# Page05_DDR4L_eMMC.net
KiCad netlist of a schematic drawn in Altium Designer
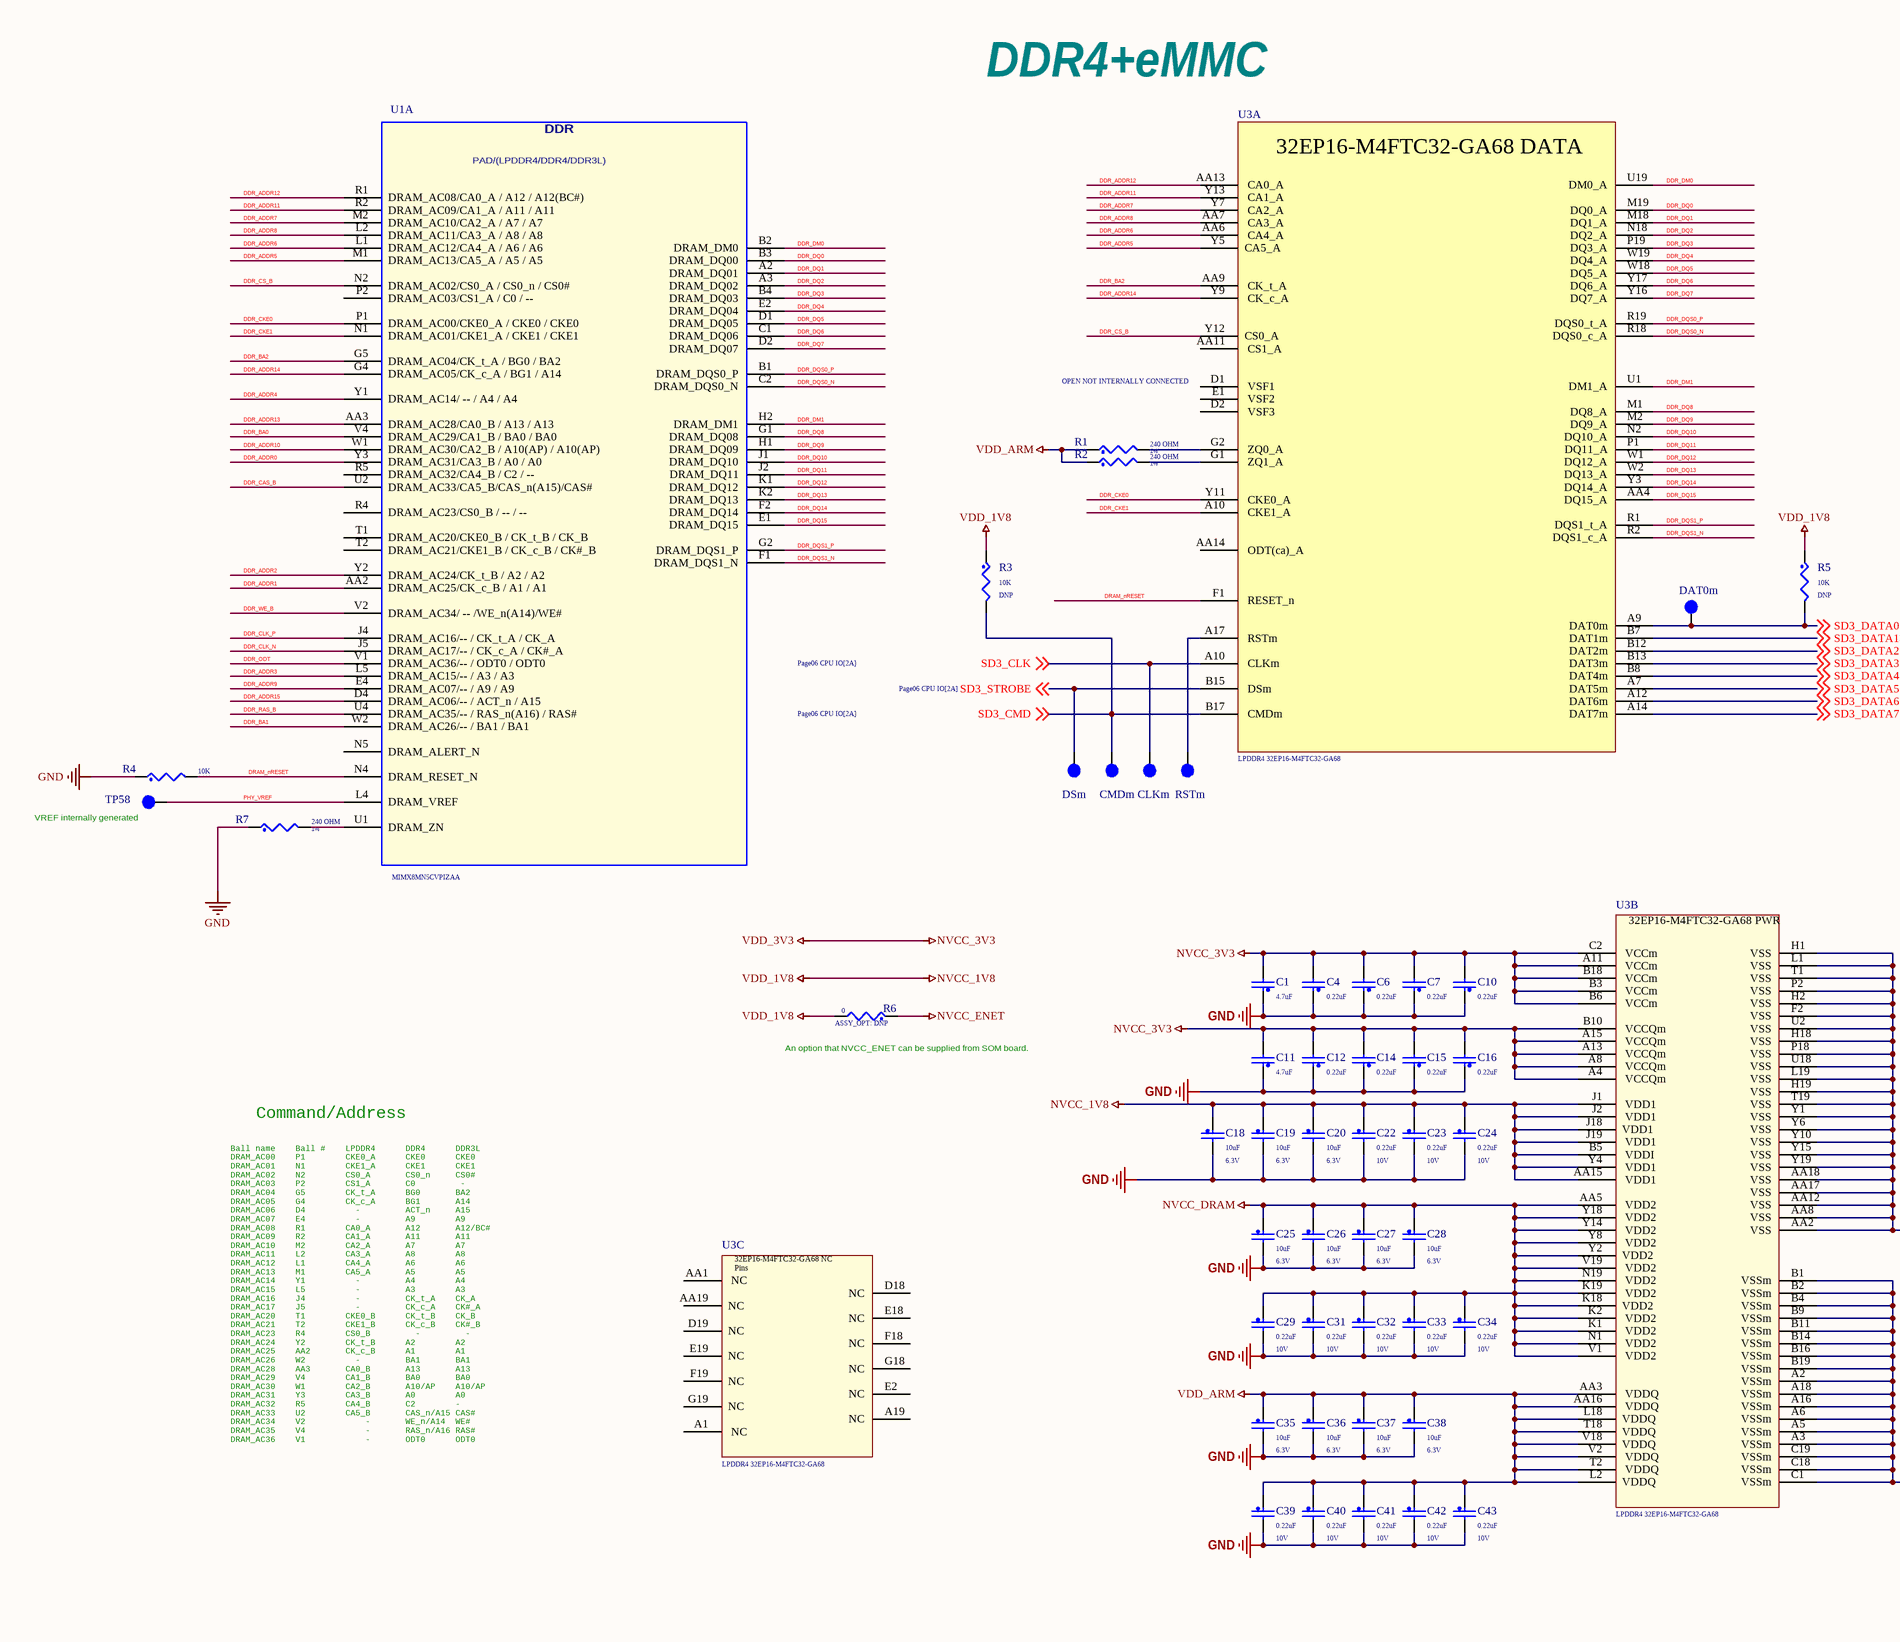
[diagram p0: Page05 DDR4L+eMMC.SchDoc, left]
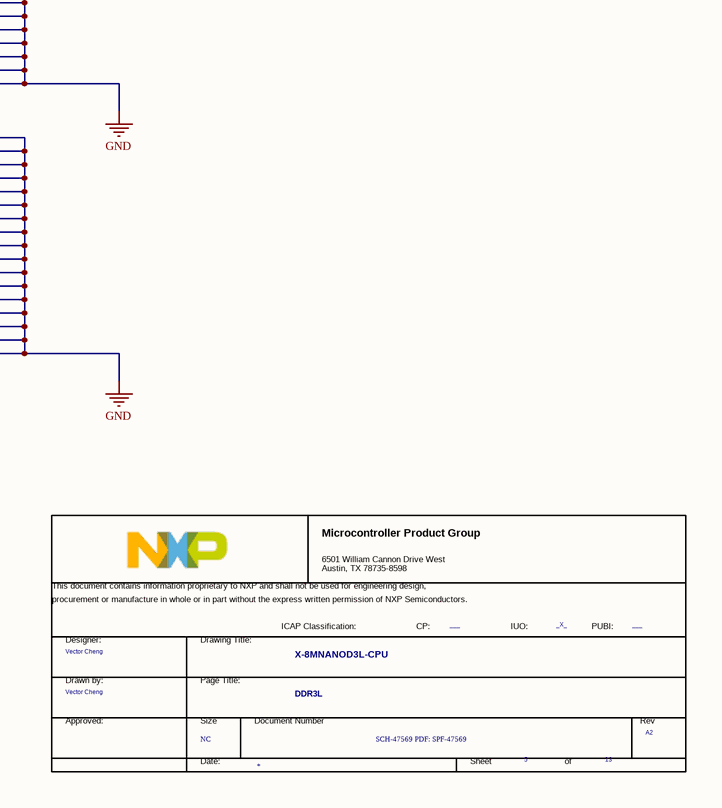
[diagram p1: Page05 DDR4L+eMMC.SchDoc, right]

(export (version "E")
  (design (tool "Eeschema 10.0.6"))
  (components
    (comp (ref "C1") (value "4.7uF") (footprint "0402_CC - C") (libsource (lib "AA_iMX8_M_") (part "CAP_NP")))
    (comp (ref "C4")
      (value "0.22uF")
      (footprint "0201_CC - C")
      (libsource (lib "AA_iMX8_M_") (part "CAP_NP"))
    )
    (comp (ref "C6")
      (value "0.22uF")
      (footprint "0201_CC - C")
      (libsource (lib "AA_iMX8_M_") (part "CAP_NP"))
    )
    (comp (ref "C7")
      (value "0.22uF")
      (footprint "0201_CC - C")
      (libsource (lib "AA_iMX8_M_") (part "CAP_NP"))
    )
    (comp (ref "C10")
      (value "0.22uF")
      (footprint "0201_CC - C")
      (libsource (lib "AA_iMX8_M_") (part "CAP_NP"))
    )
    (comp (ref "C11")
      (value "4.7uF")
      (footprint "0402_CC - C")
      (libsource (lib "AA_iMX8_M_") (part "CAP_NP"))
    )
    (comp (ref "C12")
      (value "0.22uF")
      (footprint "0201_CC - C")
      (libsource (lib "AA_iMX8_M_") (part "CAP_NP"))
    )
    (comp (ref "C14")
      (value "0.22uF")
      (footprint "0201_CC - C")
      (libsource (lib "AA_iMX8_M_") (part "CAP_NP"))
    )
    (comp (ref "C15")
      (value "0.22uF")
      (footprint "0201_CC - C")
      (libsource (lib "AA_iMX8_M_") (part "CAP_NP"))
    )
    (comp (ref "C16")
      (value "0.22uF")
      (footprint "0201_CC - C")
      (libsource (lib "AA_iMX8_M_") (part "CAP_NP"))
    )
    (comp (ref "C18")
      (value "10uF")
      (footprint "0402_CC - C")
      (fields (field (name "VOLTAGE") "6.3V"))
      (libsource (lib "AA_iMX8_M_") (part "CAP_NP"))
    )
    (comp (ref "C19")
      (value "10uF")
      (footprint "0402_CC - C")
      (fields (field (name "VOLTAGE") "6.3V"))
      (libsource (lib "AA_iMX8_M_") (part "CAP_NP"))
    )
    (comp (ref "C20")
      (value "10uF")
      (footprint "0402_CC - C")
      (fields (field (name "VOLTAGE") "6.3V"))
      (libsource (lib "AA_iMX8_M_") (part "CAP_NP"))
    )
    (comp (ref "C22")
      (value "0.22uF")
      (footprint "0201_CC - C")
      (fields (field (name "VOLTAGE") "10V"))
      (libsource (lib "AA_iMX8_M_") (part "CAP_NP"))
    )
    (comp (ref "C23")
      (value "0.22uF")
      (footprint "0201_CC - C")
      (fields (field (name "VOLTAGE") "10V"))
      (libsource (lib "AA_iMX8_M_") (part "CAP_NP"))
    )
    (comp (ref "C24")
      (value "0.22uF")
      (footprint "0201_CC - C")
      (fields (field (name "VOLTAGE") "10V"))
      (libsource (lib "AA_iMX8_M_") (part "CAP_NP"))
    )
    (comp (ref "C25")
      (value "10uF")
      (footprint "0402_CC - C")
      (fields (field (name "VOLTAGE") "6.3V"))
      (libsource (lib "AA_iMX8_M_") (part "CAP_NP"))
    )
    (comp (ref "C26")
      (value "10uF")
      (footprint "0402_CC - C")
      (fields (field (name "VOLTAGE") "6.3V"))
      (libsource (lib "AA_iMX8_M_") (part "CAP_NP"))
    )
    (comp (ref "C27")
      (value "10uF")
      (footprint "0402_CC - C")
      (fields (field (name "VOLTAGE") "6.3V"))
      (libsource (lib "AA_iMX8_M_") (part "CAP_NP"))
    )
    (comp (ref "C28")
      (value "10uF")
      (footprint "0402_CC - C")
      (fields (field (name "VOLTAGE") "6.3V"))
      (libsource (lib "AA_iMX8_M_") (part "CAP_NP"))
    )
    (comp (ref "C29")
      (value "0.22uF")
      (footprint "0201_CC - C")
      (fields (field (name "VOLTAGE") "10V"))
      (libsource (lib "AA_iMX8_M_") (part "CAP_NP"))
    )
    (comp (ref "C31")
      (value "0.22uF")
      (footprint "0201_CC - C")
      (fields (field (name "VOLTAGE") "10V"))
      (libsource (lib "AA_iMX8_M_") (part "CAP_NP"))
    )
    (comp (ref "C32")
      (value "0.22uF")
      (footprint "0201_CC - C")
      (fields (field (name "VOLTAGE") "10V"))
      (libsource (lib "AA_iMX8_M_") (part "CAP_NP"))
    )
    (comp (ref "C33")
      (value "0.22uF")
      (footprint "0201_CC - C")
      (fields (field (name "VOLTAGE") "10V"))
      (libsource (lib "AA_iMX8_M_") (part "CAP_NP"))
    )
    (comp (ref "C34")
      (value "0.22uF")
      (footprint "0201_CC - C")
      (fields (field (name "VOLTAGE") "10V"))
      (libsource (lib "AA_iMX8_M_") (part "CAP_NP"))
    )
    (comp (ref "C35")
      (value "10uF")
      (footprint "0402_CC - C")
      (fields (field (name "VOLTAGE") "6.3V"))
      (libsource (lib "AA_iMX8_M_") (part "CAP_NP"))
    )
    (comp (ref "C36")
      (value "10uF")
      (footprint "0402_CC - C")
      (fields (field (name "VOLTAGE") "6.3V"))
      (libsource (lib "AA_iMX8_M_") (part "CAP_NP"))
    )
    (comp (ref "C37")
      (value "10uF")
      (footprint "0402_CC - C")
      (fields (field (name "VOLTAGE") "6.3V"))
      (libsource (lib "AA_iMX8_M_") (part "CAP_NP"))
    )
    (comp (ref "C38")
      (value "10uF")
      (footprint "0402_CC - C")
      (fields (field (name "VOLTAGE") "6.3V"))
      (libsource (lib "AA_iMX8_M_") (part "CAP_NP"))
    )
    (comp (ref "C39")
      (value "0.22uF")
      (footprint "0201_CC - C")
      (fields (field (name "VOLTAGE") "10V"))
      (libsource (lib "AA_iMX8_M_") (part "CAP_NP"))
    )
    (comp (ref "C40")
      (value "0.22uF")
      (footprint "0201_CC - C")
      (fields (field (name "VOLTAGE") "10V"))
      (libsource (lib "AA_iMX8_M_") (part "CAP_NP"))
    )
    (comp (ref "C41")
      (value "0.22uF")
      (footprint "0201_CC - C")
      (fields (field (name "VOLTAGE") "10V"))
      (libsource (lib "AA_iMX8_M_") (part "CAP_NP"))
    )
    (comp (ref "C42")
      (value "0.22uF")
      (footprint "0201_CC - C")
      (fields (field (name "VOLTAGE") "10V"))
      (libsource (lib "AA_iMX8_M_") (part "CAP_NP"))
    )
    (comp (ref "C43")
      (value "0.22uF")
      (footprint "0201_CC - C")
      (fields (field (name "VOLTAGE") "10V"))
      (libsource (lib "AA_iMX8_M_") (part "CAP_NP"))
    )
    (comp (ref "CLKm")
      (value "tpad_020")
      (footprint "tpad_020")
      (description "TEST POINT PAD 0.5MM DIA SMT, NO PART TO ORDER")
      (libsource (lib "*") (part "TESTLOOP"))
    )
    (comp (ref "CMDm")
      (value "TPAD_015")
      (footprint "TPAD_015")
      (description "TEST POINT PAD 15MIL DIA SMT, NO PART TO ORDER")
      (libsource (lib "*") (part "TESTLOOP"))
    )
    (comp (ref "DAT0m")
      (value "tpad_020")
      (footprint "tpad_020")
      (description "TEST POINT PAD 0.5MM DIA SMT, NO PART TO ORDER")
      (libsource (lib "*") (part "TESTLOOP"))
    )
    (comp (ref "DSm")
      (value "TPAD_015")
      (footprint "TPAD_015")
      (description "TEST POINT PAD 15MIL DIA SMT, NO PART TO ORDER")
      (libsource (lib "*") (part "TESTLOOP"))
    )
    (comp (ref "R1")
      (value "240 OHM")
      (footprint "0201_RES")
      (description "RES MF 240 OHM 1/20W 1% 0201")
      (fields (field (name "VOLTAGE") "25V") (field (name "TOLERANCE") "1%"))
      (libsource (lib "*") (part "RES"))
    )
    (comp (ref "R2")
      (value "240 OHM")
      (footprint "0201_RES")
      (description "RES MF 240 OHM 1/20W 1% 0201")
      (fields (field (name "VOLTAGE") "25V") (field (name "TOLERANCE") "1%"))
      (libsource (lib "*") (part "RES"))
    )
    (comp (ref "R3")
      (value "10K")
      (footprint "0201_RES")
      (description "RES MF 10K 1/20W 5% 0201")
      (fields (field (name "ASSY_OPT") "DNP") (field (name "TOLERANCE") "5%"))
      (libsource (lib "*") (part "RES"))
    )
    (comp (ref "R4")
      (value "10K")
      (footprint "0201_RES")
      (description "RES MF 10K 1/20W 5% 0201")
      (fields (field (name "TOLERANCE") "5%"))
      (libsource (lib "*") (part "RES"))
    )
    (comp (ref "R5")
      (value "10K")
      (footprint "0201_RES")
      (description "RES MF 10K 1/20W 5% 0201")
      (fields (field (name "ASSY_OPT") "DNP") (field (name "TOLERANCE") "5%"))
      (libsource (lib "*") (part "RES"))
    )
    (comp (ref "R6")
      (value "0")
      (footprint "0402_CC_RES")
      (description "RES MF ZERO OHM 1/16W 5% 0402")
      (fields
        (field (name "ASSY_OPT") "DNP")
        (field (name "TOLERANCE") "5%")
        (field (name "VOLTAGE") "1/16W")
      )
      (libsource (lib "*") (part "RES"))
    )
    (comp (ref "R7")
      (value "240 OHM")
      (footprint "0201_RES")
      (description "RES MF 240 OHM 1/20W 1% 0201")
      (fields (field (name "VOLTAGE") "25V") (field (name "TOLERANCE") "1%"))
      (libsource (lib "*") (part "RES"))
    )
    (comp (ref "RSTm")
      (value "tpad_020")
      (footprint "tpad_020")
      (description "TEST POINT PAD 0.5MM DIA SMT, NO PART TO ORDER")
      (libsource (lib "*") (part "TESTLOOP"))
    )
    (comp (ref "TP58")
      (value "tpad_020")
      (footprint "tpad_020")
      (description "TEST POINT PAD 0.5MM DIA SMT, NO PART TO ORDER")
      (libsource (lib "*") (part "TESTLOOP"))
    )
    (comp (ref "U1")
      (value "MIMX8MN5CVPIZAA")
      (footprint "BGA306C50P21X21_1100X1100X101")
      (description "IC CPU QUAD CORTEX A53+M7 1.4GHZ -- BGA306")
      (libsource (lib "*") (part "MIMX8MN"))
    )
    (comp (ref "U3")
      (value "LPDDR4 32EP16-M4FTC32-GA68")
      (footprint "FBGA144C40P19X21_800X950X80")
      (libsource (lib "") (part "LPDDR4 32EP16-M4FTC32-GA68_1"))
    )
  )
  (nets
    (net (code "1") (name "/DDR_ADDR0") (class "Default")
      (node (ref "U1") (pin "Y3") (pinfunction "DRAM_AC31/CA3_B_/_A0_/_A0_Y3") (pintype "passive"))
    )
    (net (code "2") (name "/DDR_ADDR1") (class "Default")
      (node (ref "U1") (pin "AA2") (pinfunction "DRAM_AC25/CK_c_B_/_A1_/_A1_AA2") (pintype "passive"))
    )
    (net (code "3") (name "/DDR_ADDR2") (class "Default")
      (node (ref "U1") (pin "Y2") (pinfunction "DRAM_AC24/CK_t_B_/_A2_/_A2_Y2") (pintype "passive"))
    )
    (net (code "4") (name "/DDR_ADDR3") (class "Default")
      (node (ref "U1") (pin "L5") (pinfunction "DRAM_AC15/--_/_A3_/_A3_L5") (pintype "passive"))
    )
    (net (code "5") (name "/DDR_ADDR4") (class "Default")
      (node (ref "U1") (pin "Y1") (pinfunction "DRAM_AC14/_--_/_A4_/_A4_Y1") (pintype "passive"))
    )
    (net (code "6") (name "/DDR_ADDR5") (class "Default")
      (node (ref "U1") (pin "M1") (pinfunction "DRAM_AC13/CA5_A_/_A5_/_A5_M1") (pintype "passive"))
      (node (ref "U3") (pin "Y5") (pinfunction "CA5_A_Y5") (pintype "passive"))
    )
    (net (code "7") (name "/DDR_ADDR6") (class "Default")
      (node (ref "U1") (pin "L1") (pinfunction "DRAM_AC12/CA4_A_/_A6_/_A6_L1") (pintype "passive"))
      (node (ref "U3") (pin "AA6") (pinfunction "_CA4_A_AA6") (pintype "passive"))
    )
    (net (code "8") (name "/DDR_ADDR7") (class "Default")
      (node (ref "U1") (pin "M2") (pinfunction "DRAM_AC10/CA2_A_/_A7_/_A7_M2") (pintype "passive"))
      (node (ref "U3") (pin "Y7") (pinfunction "_CA2_A_Y7") (pintype "passive"))
    )
    (net (code "9") (name "/DDR_ADDR8") (class "Default")
      (node (ref "U1") (pin "L2") (pinfunction "DRAM_AC11/CA3_A_/_A8_/_A8_L2") (pintype "passive"))
      (node (ref "U3") (pin "AA7") (pinfunction "_CA3_A_AA7") (pintype "passive"))
    )
    (net (code "10") (name "/DDR_ADDR9") (class "Default")
      (node (ref "U1") (pin "E4") (pinfunction "DRAM_AC07/--_/_A9_/_A9_E4") (pintype "passive"))
    )
    (net (code "11") (name "/DDR_ADDR10") (class "Default")
      (node (ref "U1") (pin "W1") (pinfunction "DRAM_AC30/CA2_B_/_A10(AP)_/_A10(AP)_W1") (pintype "passive"))
    )
    (net (code "12") (name "/DDR_ADDR11") (class "Default")
      (node (ref "U1") (pin "R2") (pinfunction "DRAM_AC09/CA1_A_/_A11_/_A11_R2") (pintype "passive"))
      (node (ref "U3") (pin "Y13") (pinfunction "_CA1_A_Y13") (pintype "passive"))
    )
    (net (code "13") (name "/DDR_ADDR12") (class "Default")
      (node (ref "U1") (pin "R1") (pinfunction "DRAM_AC08/CA0_A_/_A12_/_A12(BC#)_R1") (pintype "passive"))
      (node (ref "U3") (pin "AA13") (pinfunction "_CA0_A_AA13") (pintype "passive"))
    )
    (net (code "14") (name "/DDR_ADDR13") (class "Default")
      (node (ref "U1") (pin "AA3") (pinfunction "DRAM_AC28/CA0_B_/_A13_/_A13_AA3") (pintype "passive"))
    )
    (net (code "15") (name "/DDR_ADDR14") (class "Default")
      (node (ref "U1") (pin "G4") (pinfunction "DRAM_AC05/CK_c_A_/_BG1_/_A14_G4") (pintype "passive"))
      (node (ref "U3") (pin "Y9") (pinfunction "_CK_c_A_Y9") (pintype "passive"))
    )
    (net (code "16") (name "/DDR_ADDR15") (class "Default")
      (node (ref "U1") (pin "D4") (pinfunction "DRAM_AC06/--_/_ACT_n_/_A15_D4") (pintype "passive"))
    )
    (net (code "17") (name "/DDR_BA0") (class "Default")
      (node (ref "U1") (pin "V4") (pinfunction "DRAM_AC29/CA1_B_/_BA0_/_BA0_V4") (pintype "passive"))
    )
    (net (code "18") (name "/DDR_BA1") (class "Default")
      (node (ref "U1") (pin "W2") (pinfunction "DRAM_AC26/--_/_BA1_/_BA1_W2") (pintype "passive"))
    )
    (net (code "19") (name "/DDR_BA2") (class "Default")
      (node (ref "U1") (pin "G5") (pinfunction "DRAM_AC04/CK_t_A_/_BG0_/_BA2_G5") (pintype "passive"))
      (node (ref "U3") (pin "AA9") (pinfunction "_CK_t_A_AA9") (pintype "passive"))
    )
    (net (code "20") (name "/DDR_CAS_B") (class "Default")
      (node (ref "U1") (pin "U2") (pinfunction "DRAM_AC33/CA5_B/CAS_n(A15)/CAS#_U2") (pintype "passive"))
    )
    (net (code "21") (name "/DDR_CKE0") (class "Default")
      (node (ref "U1") (pin "P1") (pinfunction "DRAM_AC00/CKE0_A_/_CKE0_/_CKE0_P1") (pintype "passive"))
      (node (ref "U3") (pin "Y11") (pinfunction "_CKE0_A_Y11") (pintype "passive"))
    )
    (net (code "22") (name "/DDR_CKE1") (class "Default")
      (node (ref "U1") (pin "N1") (pinfunction "DRAM_AC01/CKE1_A_/_CKE1_/_CKE1_N1") (pintype "passive"))
      (node (ref "U3") (pin "A10") (pinfunction "_CKE1_A_A10") (pintype "passive"))
    )
    (net (code "23") (name "/DDR_CLK_N") (class "Default")
      (node (ref "U1") (pin "J5") (pinfunction "DRAM_AC17/--_/_CK_c_A_/_CK#_A_J5") (pintype "passive"))
    )
    (net (code "24") (name "/DDR_CLK_P") (class "Default")
      (node (ref "U1") (pin "J4") (pinfunction "DRAM_AC16/--_/_CK_t_A_/_CK_A_J4") (pintype "passive"))
    )
    (net (code "25") (name "/DDR_CS_B") (class "Default")
      (node (ref "U1") (pin "N2") (pinfunction "DRAM_AC02/CS0_A_/_CS0_n_/_CS0#_N2") (pintype "passive"))
      (node (ref "U3") (pin "Y12") (pinfunction "CS0_A_Y12") (pintype "passive"))
    )
    (net (code "26") (name "/DDR_DM0") (class "Default")
      (node (ref "U1") (pin "B2") (pinfunction "DRAM_DM0_B2") (pintype "passive"))
      (node (ref "U3") (pin "U19") (pinfunction "_DM0_A_U19") (pintype "passive"))
    )
    (net (code "27") (name "/DDR_DM1") (class "Default")
      (node (ref "U1") (pin "H2") (pinfunction "DRAM_DM1_H2") (pintype "passive"))
      (node (ref "U3") (pin "U1") (pinfunction "_DM1_A_U1") (pintype "passive"))
    )
    (net (code "28") (name "/DDR_DQ0") (class "Default")
      (node (ref "U1") (pin "B3") (pinfunction "DRAM_DQ00_B3") (pintype "passive"))
      (node (ref "U3") (pin "M19") (pinfunction "_DQ0_A_M19") (pintype "passive"))
    )
    (net (code "29") (name "/DDR_DQ1") (class "Default")
      (node (ref "U1") (pin "A2") (pinfunction "DRAM_DQ01_A2") (pintype "passive"))
      (node (ref "U3") (pin "M18") (pinfunction "DQ1_A_M18") (pintype "passive"))
    )
    (net (code "30") (name "/DDR_DQ2") (class "Default")
      (node (ref "U1") (pin "A3") (pinfunction "DRAM_DQ02_A3") (pintype "passive"))
      (node (ref "U3") (pin "N18") (pinfunction "DQ2_A_N18") (pintype "passive"))
    )
    (net (code "31") (name "/DDR_DQ3") (class "Default")
      (node (ref "U1") (pin "B4") (pinfunction "DRAM_DQ03_B4") (pintype "passive"))
      (node (ref "U3") (pin "P19") (pinfunction "DQ3_A_P19") (pintype "passive"))
    )
    (net (code "32") (name "/DDR_DQ4") (class "Default")
      (node (ref "U1") (pin "E2") (pinfunction "DRAM_DQ04_E2") (pintype "passive"))
      (node (ref "U3") (pin "W19") (pinfunction "_DQ4_A_W19") (pintype "passive"))
    )
    (net (code "33") (name "/DDR_DQ5") (class "Default")
      (node (ref "U1") (pin "D1") (pinfunction "DRAM_DQ05_D1") (pintype "passive"))
      (node (ref "U3") (pin "W18") (pinfunction "DQ5_A_W18") (pintype "passive"))
    )
    (net (code "34") (name "/DDR_DQ6") (class "Default")
      (node (ref "U1") (pin "C1") (pinfunction "DRAM_DQ06_C1") (pintype "passive"))
      (node (ref "U3") (pin "Y17") (pinfunction "_DQ6_A_Y17") (pintype "passive"))
    )
    (net (code "35") (name "/DDR_DQ7") (class "Default")
      (node (ref "U1") (pin "D2") (pinfunction "DRAM_DQ07_D2") (pintype "passive"))
      (node (ref "U3") (pin "Y16") (pinfunction "_DQ7_A_Y16") (pintype "passive"))
    )
    (net (code "36") (name "/DDR_DQ8") (class "Default")
      (node (ref "U1") (pin "G1") (pinfunction "DRAM_DQ08_G1") (pintype "passive"))
      (node (ref "U3") (pin "M1") (pinfunction "_DQ8_A_M1") (pintype "passive"))
    )
    (net (code "37") (name "/DDR_DQ9") (class "Default")
      (node (ref "U1") (pin "H1") (pinfunction "DRAM_DQ09_H1") (pintype "passive"))
      (node (ref "U3") (pin "M2") (pinfunction "_DQ9_A_M2") (pintype "passive"))
    )
    (net (code "38") (name "/DDR_DQ10") (class "Default")
      (node (ref "U1") (pin "J1") (pinfunction "DRAM_DQ10_J1") (pintype "passive"))
      (node (ref "U3") (pin "N2") (pinfunction "_DQ10_A_N2") (pintype "passive"))
    )
    (net (code "39") (name "/DDR_DQ11") (class "Default")
      (node (ref "U1") (pin "J2") (pinfunction "DRAM_DQ11_J2") (pintype "passive"))
      (node (ref "U3") (pin "P1") (pinfunction "_DQ11_A_P1") (pintype "passive"))
    )
    (net (code "40") (name "/DDR_DQ12") (class "Default")
      (node (ref "U1") (pin "K1") (pinfunction "DRAM_DQ12_K1") (pintype "passive"))
      (node (ref "U3") (pin "W1") (pinfunction "_DQ12_A_W1") (pintype "passive"))
    )
    (net (code "41") (name "/DDR_DQ13") (class "Default")
      (node (ref "U1") (pin "K2") (pinfunction "DRAM_DQ13_K2") (pintype "passive"))
      (node (ref "U3") (pin "W2") (pinfunction "_DQ13_A_W2") (pintype "passive"))
    )
    (net (code "42") (name "/DDR_DQ14") (class "Default")
      (node (ref "U1") (pin "F2") (pinfunction "DRAM_DQ14_F2") (pintype "passive"))
      (node (ref "U3") (pin "Y3") (pinfunction "_DQ14_A_Y3") (pintype "passive"))
    )
    (net (code "43") (name "/DDR_DQ15") (class "Default")
      (node (ref "U1") (pin "E1") (pinfunction "DRAM_DQ15_E1") (pintype "passive"))
      (node (ref "U3") (pin "AA4") (pinfunction "_DQ15_A_AA4") (pintype "passive"))
    )
    (net (code "44") (name "/DDR_DQS0_N") (class "Default")
      (node (ref "U1") (pin "C2") (pinfunction "DRAM_DQS0_N_C2") (pintype "passive"))
      (node (ref "U3") (pin "R18") (pinfunction "DQS0_c_A_R18") (pintype "passive"))
    )
    (net (code "45") (name "/DDR_DQS0_P") (class "Default")
      (node (ref "U1") (pin "B1") (pinfunction "DRAM_DQS0_P_B1") (pintype "passive"))
      (node (ref "U3") (pin "R19") (pinfunction "_DQS0_t_A_R19") (pintype "passive"))
    )
    (net (code "46") (name "/DDR_DQS1_N") (class "Default")
      (node (ref "U1") (pin "F1") (pinfunction "DRAM_DQS1_N_F1") (pintype "passive"))
      (node (ref "U3") (pin "R2") (pinfunction "_DQS1_c_A_R2") (pintype "passive"))
    )
    (net (code "47") (name "/DDR_DQS1_P") (class "Default")
      (node (ref "U1") (pin "G2") (pinfunction "DRAM_DQS1_P_G2") (pintype "passive"))
      (node (ref "U3") (pin "R1") (pinfunction "_DQS1_t_A_R1") (pintype "passive"))
    )
    (net (code "48") (name "/DDR_ODT") (class "Default")
      (node (ref "U1") (pin "V1") (pinfunction "DRAM_AC36/--_/_ODT0_/_ODT0_V1") (pintype "passive"))
    )
    (net (code "49") (name "/DDR_RAS_B") (class "Default")
      (node (ref "U1") (pin "U4") (pinfunction "DRAM_AC35/--_/_RAS_n(A16)_/_RAS#_U4") (pintype "passive"))
    )
    (net (code "50") (name "/DDR_WE_B") (class "Default")
      (node (ref "U1") (pin "V2") (pinfunction "DRAM_AC34/_--_/WE_n(A14)/WE#_V2") (pintype "passive"))
    )
    (net (code "51") (name "/DRAM_nRESET") (class "Default")
      (node (ref "R4") (pin "2") (pinfunction "2_2") (pintype "passive"))
      (node (ref "U1") (pin "N4") (pinfunction "DRAM_RESET_N_N4") (pintype "passive"))
      (node (ref "U3") (pin "F1") (pinfunction "_RESET_n_F1") (pintype "passive"))
    )
    (net (code "52") (name "/PHY_VREF") (class "Default")
      (node (ref "TP58") (pin "1") (pinfunction "Pin1_1") (pintype "passive"))
      (node (ref "U1") (pin "L4") (pinfunction "DRAM_VREF_L4") (pintype "passive"))
    )
    (net (code "53") (name "GND") (class "Default")
      (node (ref "C1") (pin "1") (pinfunction "1_1") (pintype "passive"))
      (node (ref "C10") (pin "1") (pinfunction "1_1") (pintype "passive"))
      (node (ref "C11") (pin "1") (pinfunction "1_1") (pintype "passive"))
      (node (ref "C12") (pin "1") (pinfunction "1_1") (pintype "passive"))
      (node (ref "C14") (pin "1") (pinfunction "1_1") (pintype "passive"))
      (node (ref "C15") (pin "1") (pinfunction "1_1") (pintype "passive"))
      (node (ref "C16") (pin "1") (pinfunction "1_1") (pintype "passive"))
      (node (ref "C18") (pin "2") (pinfunction "2_2") (pintype "passive"))
      (node (ref "C19") (pin "2") (pinfunction "2_2") (pintype "passive"))
      (node (ref "C20") (pin "2") (pinfunction "2_2") (pintype "passive"))
      (node (ref "C22") (pin "2") (pinfunction "2_2") (pintype "passive"))
      (node (ref "C23") (pin "2") (pinfunction "2_2") (pintype "passive"))
      (node (ref "C24") (pin "2") (pinfunction "2_2") (pintype "passive"))
      (node (ref "C25") (pin "2") (pinfunction "2_2") (pintype "passive"))
      (node (ref "C26") (pin "2") (pinfunction "2_2") (pintype "passive"))
      (node (ref "C27") (pin "2") (pinfunction "2_2") (pintype "passive"))
      (node (ref "C28") (pin "2") (pinfunction "2_2") (pintype "passive"))
      (node (ref "C29") (pin "2") (pinfunction "2_2") (pintype "passive"))
      (node (ref "C31") (pin "2") (pinfunction "2_2") (pintype "passive"))
      (node (ref "C32") (pin "2") (pinfunction "2_2") (pintype "passive"))
      (node (ref "C33") (pin "2") (pinfunction "2_2") (pintype "passive"))
      (node (ref "C34") (pin "2") (pinfunction "2_2") (pintype "passive"))
      (node (ref "C35") (pin "2") (pinfunction "2_2") (pintype "passive"))
      (node (ref "C36") (pin "2") (pinfunction "2_2") (pintype "passive"))
      (node (ref "C37") (pin "2") (pinfunction "2_2") (pintype "passive"))
      (node (ref "C38") (pin "2") (pinfunction "2_2") (pintype "passive"))
      (node (ref "C39") (pin "2") (pinfunction "2_2") (pintype "passive"))
      (node (ref "C4") (pin "1") (pinfunction "1_1") (pintype "passive"))
      (node (ref "C40") (pin "2") (pinfunction "2_2") (pintype "passive"))
      (node (ref "C41") (pin "2") (pinfunction "2_2") (pintype "passive"))
      (node (ref "C42") (pin "2") (pinfunction "2_2") (pintype "passive"))
      (node (ref "C43") (pin "2") (pinfunction "2_2") (pintype "passive"))
      (node (ref "C6") (pin "1") (pinfunction "1_1") (pintype "passive"))
      (node (ref "C7") (pin "1") (pinfunction "1_1") (pintype "passive"))
      (node (ref "R4") (pin "1") (pinfunction "1_1") (pintype "passive"))
      (node (ref "R7") (pin "1") (pinfunction "1_1") (pintype "passive"))
      (node (ref "U3") (pin "A16") (pinfunction "_VSSm_A16") (pintype "power_in"))
      (node (ref "U3") (pin "A18") (pinfunction "_VSSm_A18") (pintype "power_in"))
      (node (ref "U3") (pin "A2") (pinfunction "_VSSm_A2") (pintype "power_in"))
      (node (ref "U3") (pin "A3") (pinfunction "VSSm_A3") (pintype "power_in"))
      (node (ref "U3") (pin "A5") (pinfunction "_VSSm_A5") (pintype "power_in"))
      (node (ref "U3") (pin "A6") (pinfunction "_VSSm_A6") (pintype "power_in"))
      (node (ref "U3") (pin "AA12") (pinfunction "_VSS_AA12") (pintype "power_in"))
      (node (ref "U3") (pin "AA17") (pinfunction "_VSS_AA17") (pintype "power_in"))
      (node (ref "U3") (pin "AA18") (pinfunction "VSS_AA18") (pintype "power_in"))
      (node (ref "U3") (pin "AA2") (pinfunction "VSS_AA2") (pintype "power_in"))
      (node (ref "U3") (pin "AA8") (pinfunction "_VSS_AA8") (pintype "power_in"))
      (node (ref "U3") (pin "B1") (pinfunction "_VSSm_B1") (pintype "power_in"))
      (node (ref "U3") (pin "B11") (pinfunction "_VSSm_B11") (pintype "power_in"))
      (node (ref "U3") (pin "B14") (pinfunction "_VSSm_B14") (pintype "power_in"))
      (node (ref "U3") (pin "B16") (pinfunction "_VSSm_B16") (pintype "power_in"))
      (node (ref "U3") (pin "B19") (pinfunction "_VSSm_B19") (pintype "power_in"))
      (node (ref "U3") (pin "B2") (pinfunction "_VSSm_B2") (pintype "power_in"))
      (node (ref "U3") (pin "B4") (pinfunction "_VSSm_B4") (pintype "power_in"))
      (node (ref "U3") (pin "B9") (pinfunction "_VSSm_B9") (pintype "power_in"))
      (node (ref "U3") (pin "C1") (pinfunction "_VSSm_C1") (pintype "power_in"))
      (node (ref "U3") (pin "C18") (pinfunction "VSSm_C18") (pintype "power_in"))
      (node (ref "U3") (pin "C19") (pinfunction "_VSSm_C19") (pintype "power_in"))
      (node (ref "U3") (pin "F2") (pinfunction "_VSS_F2") (pintype "power_in"))
      (node (ref "U3") (pin "H1") (pinfunction "_VSS_H1") (pintype "power_in"))
      (node (ref "U3") (pin "H18") (pinfunction "VSS_H18") (pintype "power_in"))
      (node (ref "U3") (pin "H19") (pinfunction "VSS_H19") (pintype "power_in"))
      (node (ref "U3") (pin "H2") (pinfunction "VSS_H2") (pintype "power_in"))
      (node (ref "U3") (pin "L1") (pinfunction "_VSS_L1") (pintype "power_in"))
      (node (ref "U3") (pin "L19") (pinfunction "VSS_L19") (pintype "power_in"))
      (node (ref "U3") (pin "P18") (pinfunction "VSS_P18") (pintype "power_in"))
      (node (ref "U3") (pin "P2") (pinfunction "_VSS_P2") (pintype "power_in"))
      (node (ref "U3") (pin "T1") (pinfunction "_VSS_T1") (pintype "power_in"))
      (node (ref "U3") (pin "T19") (pinfunction "VSS_T19") (pintype "power_in"))
      (node (ref "U3") (pin "U18") (pinfunction "VSS_U18") (pintype "power_in"))
      (node (ref "U3") (pin "U2") (pinfunction "_VSS_U2") (pintype "power_in"))
      (node (ref "U3") (pin "Y1") (pinfunction "_VSS_Y1") (pintype "power_in"))
      (node (ref "U3") (pin "Y10") (pinfunction "_VSS_Y10") (pintype "power_in"))
      (node (ref "U3") (pin "Y15") (pinfunction "_VSS_Y15") (pintype "power_in"))
      (node (ref "U3") (pin "Y19") (pinfunction "VSS_Y19") (pintype "power_in"))
      (node (ref "U3") (pin "Y6") (pinfunction "_VSS_Y6") (pintype "power_in"))
    )
    (net (code "54") (name "NVCC_1V8") (class "Default")
      (node (ref "C18") (pin "1") (pinfunction "1_1") (pintype "passive"))
      (node (ref "C19") (pin "1") (pinfunction "1_1") (pintype "passive"))
      (node (ref "C20") (pin "1") (pinfunction "1_1") (pintype "passive"))
      (node (ref "C22") (pin "1") (pinfunction "1_1") (pintype "passive"))
      (node (ref "C23") (pin "1") (pinfunction "1_1") (pintype "passive"))
      (node (ref "C24") (pin "1") (pinfunction "1_1") (pintype "passive"))
      (node (ref "R3") (pin "1") (pinfunction "1_1") (pintype "passive"))
      (node (ref "R5") (pin "1") (pinfunction "1_1") (pintype "passive"))
      (node (ref "R6") (pin "2") (pinfunction "2_2") (pintype "passive"))
      (node (ref "U3") (pin "AA15") (pinfunction "_VDD1_AA15") (pintype "power_in"))
      (node (ref "U3") (pin "B5") (pinfunction "_VDDI_B5") (pintype "power_in"))
      (node (ref "U3") (pin "J1") (pinfunction "_VDD1_J1") (pintype "power_in"))
      (node (ref "U3") (pin "J18") (pinfunction "VDD1_J18") (pintype "power_in"))
      (node (ref "U3") (pin "J19") (pinfunction "_VDD1_J19") (pintype "power_in"))
      (node (ref "U3") (pin "J2") (pinfunction "_VDD1_J2") (pintype "power_in"))
      (node (ref "U3") (pin "Y4") (pinfunction "_VDD1_Y4") (pintype "power_in"))
    )
    (net (code "55") (name "NVCC_3V3") (class "Default")
      (node (ref "C1") (pin "2") (pinfunction "2_2") (pintype "passive"))
      (node (ref "C10") (pin "2") (pinfunction "2_2") (pintype "passive"))
      (node (ref "C11") (pin "2") (pinfunction "2_2") (pintype "passive"))
      (node (ref "C12") (pin "2") (pinfunction "2_2") (pintype "passive"))
      (node (ref "C14") (pin "2") (pinfunction "2_2") (pintype "passive"))
      (node (ref "C15") (pin "2") (pinfunction "2_2") (pintype "passive"))
      (node (ref "C16") (pin "2") (pinfunction "2_2") (pintype "passive"))
      (node (ref "C4") (pin "2") (pinfunction "2_2") (pintype "passive"))
      (node (ref "C6") (pin "2") (pinfunction "2_2") (pintype "passive"))
      (node (ref "C7") (pin "2") (pinfunction "2_2") (pintype "passive"))
      (node (ref "U3") (pin "A11") (pinfunction "_VCCm_A11") (pintype "power_in"))
      (node (ref "U3") (pin "A13") (pinfunction "_VCCQm_A13") (pintype "power_in"))
      (node (ref "U3") (pin "A15") (pinfunction "_VCCQm_A15") (pintype "power_in"))
      (node (ref "U3") (pin "A4") (pinfunction "_VCCQm_A4") (pintype "power_in"))
      (node (ref "U3") (pin "A8") (pinfunction "_VCCQm_A8") (pintype "power_in"))
      (node (ref "U3") (pin "B10") (pinfunction "_VCCQm_B10") (pintype "power_in"))
      (node (ref "U3") (pin "B18") (pinfunction "_VCCm_B18") (pintype "power_in"))
      (node (ref "U3") (pin "B3") (pinfunction "_VCCm_B3") (pintype "power_in"))
      (node (ref "U3") (pin "B6") (pinfunction "_VCCm_B6") (pintype "power_in"))
      (node (ref "U3") (pin "C2") (pinfunction "_VCCm_C2") (pintype "power_in"))
    )
    (net (code "56") (name "NVCC_DRAM") (class "Default")
      (node (ref "C25") (pin "1") (pinfunction "1_1") (pintype "passive"))
      (node (ref "C26") (pin "1") (pinfunction "1_1") (pintype "passive"))
      (node (ref "C27") (pin "1") (pinfunction "1_1") (pintype "passive"))
      (node (ref "C28") (pin "1") (pinfunction "1_1") (pintype "passive"))
      (node (ref "C29") (pin "1") (pinfunction "1_1") (pintype "passive"))
      (node (ref "C31") (pin "1") (pinfunction "1_1") (pintype "passive"))
      (node (ref "C32") (pin "1") (pinfunction "1_1") (pintype "passive"))
      (node (ref "C33") (pin "1") (pinfunction "1_1") (pintype "passive"))
      (node (ref "C34") (pin "1") (pinfunction "1_1") (pintype "passive"))
      (node (ref "U3") (pin "AA5") (pinfunction "_VDD2_AA5") (pintype "power_in"))
      (node (ref "U3") (pin "K1") (pinfunction "_VDD2_K1") (pintype "power_in"))
      (node (ref "U3") (pin "K18") (pinfunction "VDD2_K18") (pintype "power_in"))
      (node (ref "U3") (pin "K19") (pinfunction "_VDD2_K19") (pintype "power_in"))
      (node (ref "U3") (pin "K2") (pinfunction "_VDD2_K2") (pintype "power_in"))
      (node (ref "U3") (pin "N1") (pinfunction "_VDD2_N1") (pintype "power_in"))
      (node (ref "U3") (pin "N19") (pinfunction "_VDD2_N19") (pintype "power_in"))
      (node (ref "U3") (pin "V1") (pinfunction "_VDD2_V1") (pintype "power_in"))
      (node (ref "U3") (pin "V19") (pinfunction "_VDD2_V19") (pintype "power_in"))
      (node (ref "U3") (pin "Y14") (pinfunction "_VDD2_Y14") (pintype "power_in"))
      (node (ref "U3") (pin "Y18") (pinfunction "_VDD2_Y18") (pintype "power_in"))
      (node (ref "U3") (pin "Y2") (pinfunction "VDD2_Y2") (pintype "power_in"))
      (node (ref "U3") (pin "Y8") (pinfunction "_VDD2_Y8") (pintype "power_in"))
    )
    (net (code "57") (name "NVCC_ENET") (class "Default")
      (node (ref "R6") (pin "1") (pinfunction "1_1") (pintype "passive"))
    )
    (net (code "58") (name "Net-(RSTm-Pin1)") (class "Default")
      (node (ref "RSTm") (pin "1") (pinfunction "Pin1_1") (pintype "passive"))
      (node (ref "U3") (pin "A17") (pinfunction "_RSTm_A17") (pintype "passive"))
    )
    (net (code "59") (name "Net-(U1A-DRAM_ZN)") (class "Default")
      (node (ref "R7") (pin "2") (pinfunction "2_2") (pintype "passive"))
      (node (ref "U1") (pin "U1") (pinfunction "DRAM_ZN_U1") (pintype "passive"))
    )
    (net (code "60") (name "Net-(U3A-_ZQ0_A)") (class "Default")
      (node (ref "R1") (pin "2") (pinfunction "2_2") (pintype "passive"))
      (node (ref "U3") (pin "G2") (pinfunction "_ZQ0_A_G2") (pintype "passive"))
    )
    (net (code "61") (name "Net-(U3A-_ZQ1_A)") (class "Default")
      (node (ref "R2") (pin "2") (pinfunction "2_2") (pintype "passive"))
      (node (ref "U3") (pin "G1") (pinfunction "_ZQ1_A_G1") (pintype "passive"))
    )
    (net (code "62") (name "SD3_CLK") (class "Default")
      (node (ref "CLKm") (pin "1") (pinfunction "Pin1_1") (pintype "passive"))
      (node (ref "U3") (pin "A10") (pinfunction "_CLKm_A10") (pintype "passive"))
    )
    (net (code "63") (name "SD3_CMD") (class "Default")
      (node (ref "CMDm") (pin "1") (pinfunction "Pin1_1") (pintype "passive"))
      (node (ref "R3") (pin "2") (pinfunction "2_2") (pintype "passive"))
      (node (ref "U3") (pin "B17") (pinfunction "_CMDm_B17") (pintype "passive"))
    )
    (net (code "64") (name "SD3_DATA0") (class "Default")
      (node (ref "DAT0m") (pin "1") (pinfunction "Pin1_1") (pintype "passive"))
      (node (ref "R5") (pin "2") (pinfunction "2_2") (pintype "passive"))
      (node (ref "U3") (pin "A9") (pinfunction "_DAT0m_A9") (pintype "passive"))
    )
    (net (code "65") (name "SD3_DATA1") (class "Default")
      (node (ref "U3") (pin "B7") (pinfunction "DAT1m_B7") (pintype "passive"))
    )
    (net (code "66") (name "SD3_DATA2") (class "Default")
      (node (ref "U3") (pin "B12") (pinfunction "_DAT2m_B12") (pintype "passive"))
    )
    (net (code "67") (name "SD3_DATA3") (class "Default")
      (node (ref "U3") (pin "B13") (pinfunction "_DAT3m_B13") (pintype "passive"))
    )
    (net (code "68") (name "SD3_DATA4") (class "Default")
      (node (ref "U3") (pin "B8") (pinfunction "_DAT4m_B8") (pintype "passive"))
    )
    (net (code "69") (name "SD3_DATA5") (class "Default")
      (node (ref "U3") (pin "A7") (pinfunction "_DAT5m_A7") (pintype "passive"))
    )
    (net (code "70") (name "SD3_DATA6") (class "Default")
      (node (ref "U3") (pin "A12") (pinfunction "_DAT6m_A12") (pintype "passive"))
    )
    (net (code "71") (name "SD3_DATA7") (class "Default")
      (node (ref "U3") (pin "A14") (pinfunction "_DAT7m_A14") (pintype "passive"))
    )
    (net (code "72") (name "SD3_STROBE") (class "Default")
      (node (ref "DSm") (pin "1") (pinfunction "Pin1_1") (pintype "passive"))
      (node (ref "U3") (pin "B15") (pinfunction "_DSm_B15") (pintype "passive"))
    )
    (net (code "73") (name "VDD_ARM") (class "Default")
      (node (ref "C35") (pin "1") (pinfunction "1_1") (pintype "passive"))
      (node (ref "C36") (pin "1") (pinfunction "1_1") (pintype "passive"))
      (node (ref "C37") (pin "1") (pinfunction "1_1") (pintype "passive"))
      (node (ref "C38") (pin "1") (pinfunction "1_1") (pintype "passive"))
      (node (ref "C39") (pin "1") (pinfunction "1_1") (pintype "passive"))
      (node (ref "C40") (pin "1") (pinfunction "1_1") (pintype "passive"))
      (node (ref "C41") (pin "1") (pinfunction "1_1") (pintype "passive"))
      (node (ref "C42") (pin "1") (pinfunction "1_1") (pintype "passive"))
      (node (ref "C43") (pin "1") (pinfunction "1_1") (pintype "passive"))
      (node (ref "R1") (pin "1") (pinfunction "1_1") (pintype "passive"))
      (node (ref "R2") (pin "1") (pinfunction "1_1") (pintype "passive"))
      (node (ref "U3") (pin "AA16") (pinfunction "_VDDQ_AA16") (pintype "power_in"))
      (node (ref "U3") (pin "AA3") (pinfunction "_VDDQ_AA3") (pintype "power_in"))
      (node (ref "U3") (pin "L18") (pinfunction "VDDQ_L18") (pintype "power_in"))
      (node (ref "U3") (pin "L2") (pinfunction "VDDQ_L2") (pintype "power_in"))
      (node (ref "U3") (pin "T18") (pinfunction "VDDQ_T18") (pintype "power_in"))
      (node (ref "U3") (pin "T2") (pinfunction "_VDDQ_T2") (pintype "power_in"))
      (node (ref "U3") (pin "V18") (pinfunction "VDDQ_V18") (pintype "power_in"))
      (node (ref "U3") (pin "V2") (pinfunction "_VDDQ_V2") (pintype "power_in"))
    )
    (net (code "74") (name "unconnected-(U1A-DRAM_AC03{slash}CS1_A_{slash}_C0_{slash}_---PadP2)") (class "Default")
      (node (ref "U1") (pin "P2") (pinfunction "DRAM_AC03/CS1_A_/_C0_/_--_P2") (pintype "passive"))
    )
    (net (code "75") (name "unconnected-(U1A-DRAM_AC20{slash}CKE0_B_{slash}_CK_t_B_{slash}_CK_B-PadT1)") (class "Default")
      (node (ref "U1") (pin "T1") (pinfunction "DRAM_AC20/CKE0_B_/_CK_t_B_/_CK_B_T1") (pintype "passive"))
    )
    (net (code "76") (name "unconnected-(U1A-DRAM_AC21{slash}CKE1_B_{slash}_CK_c_B_{slash}_CK#_B-PadT2)") (class "Default")
      (node (ref "U1") (pin "T2") (pinfunction "DRAM_AC21/CKE1_B_/_CK_c_B_/_CK#_B_T2") (pintype "passive"))
    )
    (net (code "77") (name "unconnected-(U1A-DRAM_AC23{slash}CS0_B_{slash}_--_{slash}_---PadR4)") (class "Default")
      (node (ref "U1") (pin "R4") (pinfunction "DRAM_AC23/CS0_B_/_--_/_--_R4") (pintype "passive"))
    )
    (net (code "78") (name "unconnected-(U1A-DRAM_AC32{slash}CA4_B_{slash}_C2_{slash}_---PadR5)") (class "Default")
      (node (ref "U1") (pin "R5") (pinfunction "DRAM_AC32/CA4_B_/_C2_/_--_R5") (pintype "passive"))
    )
    (net (code "79") (name "unconnected-(U1A-DRAM_ALERT_N-PadN5)") (class "Default")
      (node (ref "U1") (pin "N5") (pinfunction "DRAM_ALERT_N_N5") (pintype "passive"))
    )
    (net (code "80") (name "unconnected-(U3A-_CS1_A-PadAA11)") (class "Default")
      (node (ref "U3") (pin "AA11") (pinfunction "_CS1_A_AA11") (pintype "passive"))
    )
    (net (code "81") (name "unconnected-(U3A-_ODT(ca)_A-PadAA14)") (class "Default")
      (node (ref "U3") (pin "AA14") (pinfunction "_ODT(ca)_A_AA14") (pintype "passive"))
    )
    (net (code "82") (name "unconnected-(U3A-_VSF1-PadD1)") (class "Default")
      (node (ref "U3") (pin "D1") (pinfunction "_VSF1_D1") (pintype "passive"))
    )
    (net (code "83") (name "unconnected-(U3A-_VSF2-PadE1)") (class "Default")
      (node (ref "U3") (pin "E1") (pinfunction "_VSF2_E1") (pintype "passive"))
    )
    (net (code "84") (name "unconnected-(U3A-_VSF3-PadD2)") (class "Default")
      (node (ref "U3") (pin "D2") (pinfunction "_VSF3_D2") (pintype "passive"))
    )
    (net (code "85") (name "unconnected-(U3C-NC-PadA19)") (class "Default")
      (node (ref "U3") (pin "A19") (pinfunction "NC_A19") (pintype "passive"))
    )
    (net (code "86") (name "unconnected-(U3C-NC-PadAA19)") (class "Default")
      (node (ref "U3") (pin "AA19") (pinfunction "NC_AA19") (pintype "passive"))
    )
    (net (code "87") (name "unconnected-(U3C-NC-PadD18)") (class "Default")
      (node (ref "U3") (pin "D18") (pinfunction "NC_D18") (pintype "passive"))
    )
    (net (code "88") (name "unconnected-(U3C-NC-PadD19)") (class "Default")
      (node (ref "U3") (pin "D19") (pinfunction "NC_D19") (pintype "passive"))
    )
    (net (code "89") (name "unconnected-(U3C-NC-PadE2)") (class "Default")
      (node (ref "U3") (pin "E2") (pinfunction "NC_E2") (pintype "passive"))
    )
    (net (code "90") (name "unconnected-(U3C-NC-PadE18)") (class "Default")
      (node (ref "U3") (pin "E18") (pinfunction "NC_E18") (pintype "passive"))
    )
    (net (code "91") (name "unconnected-(U3C-NC-PadE19)") (class "Default")
      (node (ref "U3") (pin "E19") (pinfunction "NC_E19") (pintype "passive"))
    )
    (net (code "92") (name "unconnected-(U3C-NC-PadF18)") (class "Default")
      (node (ref "U3") (pin "F18") (pinfunction "NC_F18") (pintype "passive"))
    )
    (net (code "93") (name "unconnected-(U3C-NC-PadF19)") (class "Default")
      (node (ref "U3") (pin "F19") (pinfunction "NC_F19") (pintype "passive"))
    )
    (net (code "94") (name "unconnected-(U3C-NC-PadG18)") (class "Default")
      (node (ref "U3") (pin "G18") (pinfunction "NC_G18") (pintype "passive"))
    )
    (net (code "95") (name "unconnected-(U3C-NC-PadG19)") (class "Default")
      (node (ref "U3") (pin "G19") (pinfunction "NC_G19") (pintype "passive"))
    )
    (net (code "96") (name "unconnected-(U3C-_NC-PadA1)") (class "Default")
      (node (ref "U3") (pin "A1") (pinfunction "_NC_A1") (pintype "passive"))
    )
    (net (code "97") (name "unconnected-(U3C-_NC-PadAA1)") (class "Default")
      (node (ref "U3") (pin "AA1") (pinfunction "_NC_AA1") (pintype "passive"))
    )
  )
)
